# SSR_MODULE.net
KiCad netlist of a schematic drawn in Altium Designer
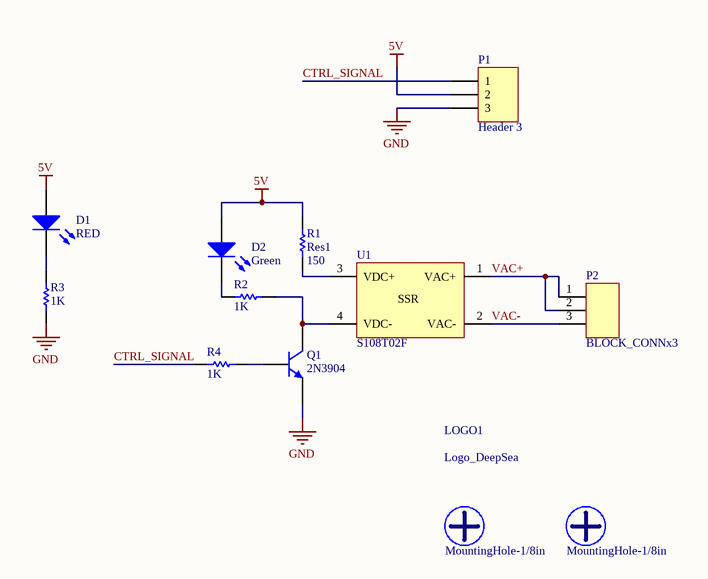
[diagram p0: SSR_MODULE.SchDoc]

(export (version "E")
  (design (tool "Eeschema 10.0.6"))
  (components
    (comp (ref "*1")
      (value "MountingHole-1/8in")
      (footprint "MoutingHole-1/8in")
      (libsource (lib "General") (part "MountingHole-1/8in"))
    )
    (comp (ref "*2")
      (value "MountingHole-1/8in")
      (footprint "MoutingHole-1/8in")
      (libsource (lib "General") (part "MountingHole-1/8in"))
    )
    (comp (ref "D1")
      (value "RED")
      (footprint "R0603_L")
      (fields (field (name "COLOR") "RED"))
      (libsource (lib "General") (part "LED_SMD"))
    )
    (comp (ref "D2")
      (value "Green")
      (footprint "R0603_L")
      (fields (field (name "COLOR") "Green"))
      (libsource (lib "General") (part "LED_SMD"))
    )
    (comp (ref "LOGO1")
      (value "Logo_DeepSea")
      (footprint "DeepSea_logo1")
      (libsource (lib "General") (part "Logo_DeepSea"))
    )
    (comp (ref "P1")
      (value "Header 3")
      (footprint "HDR1X3")
      (description "Header, 3-Pin")
      (fields (field (name "PUBLISHER") "Altium Limited"))
      (libsource (lib "Miscellaneous Connectors") (part "Header 3"))
    )
    (comp (ref "P2")
      (value "BLOCK_CONNx3")
      (footprint "BLOCK_CONNx3")
      (description "TERM BLOCK 5.08MM VERT 3POS PCB")
      (fields
        (field (name "MANUFACTURER") "On Shore Technology Inc")
        (field (name "MANUFACTURER PART NUMBER") "OSTTC032162")
      )
      (libsource (lib "General") (part "BLOCK_CONNx3"))
    )
    (comp (ref "Q1")
      (value "2N3904")
      (footprint "TO-92A")
      (description "NPN General Purpose Amplifier")
      (fields (field (name "PUBLISHER") "Altium Limited"))
      (libsource (lib "Miscellaneous Devices") (part "2N3904"))
    )
    (comp (ref "R1")
      (value "Res1")
      (footprint "AXIAL-0.3")
      (description "Resistor")
      (fields (field (name "ALTIUM_VALUE") "150") (field (name "PUBLISHER") "Altium Limited"))
      (libsource (lib "Miscellaneous Devices") (part "Res1"))
    )
    (comp (ref "R2")
      (value "1K")
      (footprint "R0603_L")
      (fields (field (name "Comment") "R_SMD"))
      (libsource (lib "General") (part "R_SMD"))
    )
    (comp (ref "R3")
      (value "1K")
      (footprint "R0603_L")
      (fields (field (name "Comment") "R_SMD"))
      (libsource (lib "General") (part "R_SMD"))
    )
    (comp (ref "R4")
      (value "1K")
      (footprint "R0603_L")
      (fields (field (name "Comment") "R_SMD"))
      (libsource (lib "General") (part "R_SMD"))
    )
    (comp (ref "U1")
      (value "S108T02F")
      (footprint "ZC_4-ZSIP")
      (description "RELAY SSR 120VAC 8A ZC 4-SIP")
      (fields (field (name "MANUFACTURER") "Sharp Microelectronics"))
      (libsource (lib "General") (part "S108T02F"))
    )
  )
  (nets
    (net (code "1") (name "/CTRL_SIGNAL") (class "Default")
      (node (ref "P1") (pin "1") (pinfunction "1_1") (pintype "passive"))
      (node (ref "R4") (pin "2") (pinfunction "2_2") (pintype "passive"))
    )
    (net (code "2") (name "/VAC+") (class "Default")
      (node (ref "P2") (pin "1") (pintype "passive"))
      (node (ref "P2") (pin "2") (pintype "passive"))
      (node (ref "U1") (pin "1") (pinfunction "VAC+_1") (pintype "passive"))
    )
    (net (code "3") (name "/VAC-") (class "Default")
      (node (ref "P2") (pin "3") (pintype "passive"))
      (node (ref "U1") (pin "2") (pinfunction "VAC-_2") (pintype "passive"))
    )
    (net (code "4") (name "5V") (class "Default")
      (node (ref "D1") (pin "1") (pinfunction "A_1") (pintype "passive"))
      (node (ref "D2") (pin "1") (pinfunction "A_1") (pintype "passive"))
      (node (ref "P1") (pin "2") (pinfunction "2_2") (pintype "passive"))
      (node (ref "R1") (pin "2") (pinfunction "2_2") (pintype "passive"))
    )
    (net (code "5") (name "GND") (class "Default")
      (node (ref "P1") (pin "3") (pinfunction "3_3") (pintype "passive"))
      (node (ref "Q1") (pin "1") (pinfunction "E_1") (pintype "passive"))
      (node (ref "R3") (pin "2") (pinfunction "2_2") (pintype "passive"))
    )
    (net (code "6") (name "Net-(D1-K)") (class "Default")
      (node (ref "D1") (pin "2") (pinfunction "K_2") (pintype "passive"))
      (node (ref "R3") (pin "1") (pinfunction "1_1") (pintype "passive"))
    )
    (net (code "7") (name "Net-(D2-K)") (class "Default")
      (node (ref "D2") (pin "2") (pinfunction "K_2") (pintype "passive"))
      (node (ref "R2") (pin "2") (pinfunction "2_2") (pintype "passive"))
    )
    (net (code "8") (name "Net-(Q1-B)") (class "Default")
      (node (ref "Q1") (pin "2") (pinfunction "B_2") (pintype "passive"))
      (node (ref "R4") (pin "1") (pinfunction "1_1") (pintype "passive"))
    )
    (net (code "9") (name "Net-(Q1-C)") (class "Default")
      (node (ref "Q1") (pin "3") (pinfunction "C_3") (pintype "passive"))
      (node (ref "R2") (pin "1") (pinfunction "1_1") (pintype "passive"))
      (node (ref "U1") (pin "4") (pinfunction "VDC-_4") (pintype "passive"))
    )
    (net (code "10") (name "Net-(U1-VDC+)") (class "Default")
      (node (ref "R1") (pin "1") (pinfunction "1_1") (pintype "passive"))
      (node (ref "U1") (pin "3") (pinfunction "VDC+_3") (pintype "passive"))
    )
  )
)
